# Schematic.net
KiCad netlist of a schematic drawn in Altium Designer
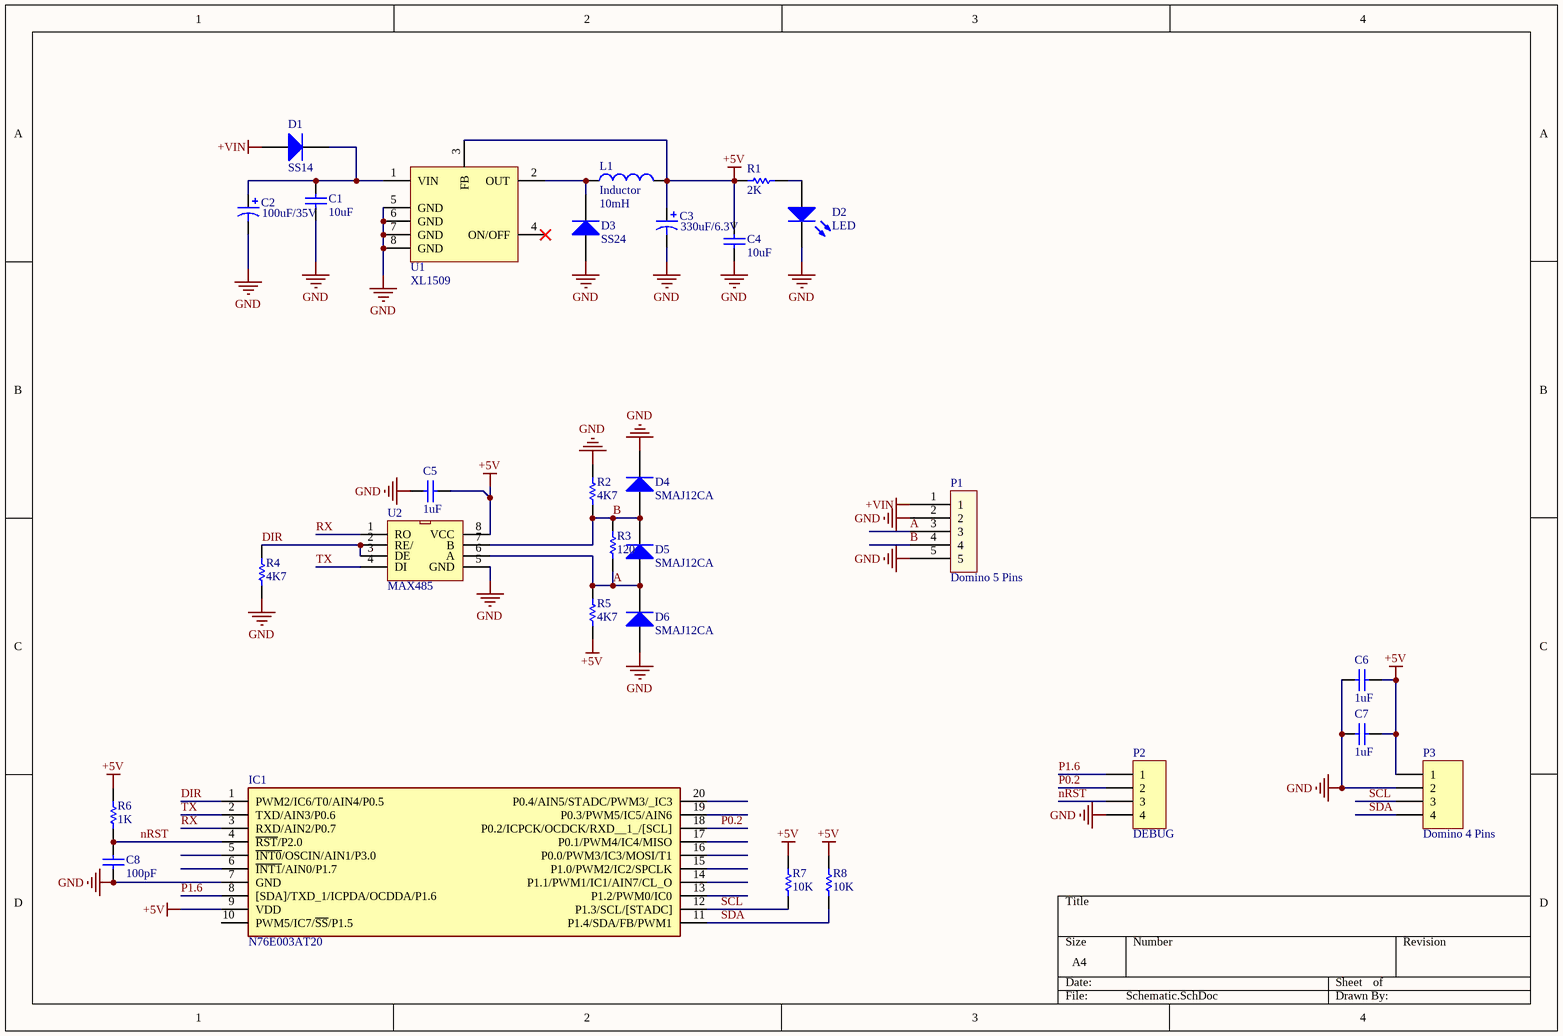
[diagram p0: Schematic.SchDoc]

(export (version "E")
  (design (tool "Eeschema 10.0.6"))
  (components
    (comp (ref "C1")
      (value "10uF")
      (footprint "MinhTien_PcbLib:CAPC1608L")
      (description "Capacitor")
      (fields (field (name "PUBLISHER") "Altium Limited"))
      (libsource (lib "MinhTien_SCHLib") (part "Cap"))
    )
    (comp (ref "C2")
      (value "100uF/35V")
      (footprint "MinhTien_PcbLib:Tu Nhom SMD_D8 6.3x7.7mm")
      (description "Polarized Capacitor (Axial)")
      (fields (field (name "Comment") "Cap Pol2") (field (name "PUBLISHER") "Altium Limited"))
      (libsource (lib "MinhTien_SCHLib") (part "Cap Pol2"))
    )
    (comp (ref "C3")
      (value "330uF/6.3V")
      (footprint "MinhTien_PcbLib:Tu Nhom SMD_D8 6.3x7.7mm")
      (description "Polarized Capacitor (Axial)")
      (fields (field (name "Comment") "Cap Pol2") (field (name "PUBLISHER") "Altium Limited"))
      (libsource (lib "MinhTien_SCHLib") (part "Cap Pol2"))
    )
    (comp (ref "C4")
      (value "10uF")
      (footprint "MinhTien_PcbLib:CAPC1608L")
      (description "Capacitor")
      (fields (field (name "PUBLISHER") "Altium Limited"))
      (libsource (lib "MinhTien_SCHLib") (part "Cap"))
    )
    (comp (ref "C5")
      (value "1uF")
      (footprint "MinhTien_PcbLib:CAPC1608L")
      (description "Capacitor")
      (fields (field (name "PUBLISHER") "Altium Limited"))
      (libsource (lib "MinhTien_SCHLib") (part "Cap"))
    )
    (comp (ref "C6")
      (value "1uF")
      (footprint "MinhTien_PcbLib:CAPC1608L")
      (description "Capacitor")
      (fields (field (name "PUBLISHER") "Altium Limited"))
      (libsource (lib "MinhTien_SCHLib") (part "Cap"))
    )
    (comp (ref "C7")
      (value "1uF")
      (footprint "MinhTien_PcbLib:CAPC1608L")
      (description "Capacitor")
      (fields (field (name "PUBLISHER") "Altium Limited"))
      (libsource (lib "MinhTien_SCHLib") (part "Cap"))
    )
    (comp (ref "C8")
      (value "100pF")
      (footprint "MinhTien_PcbLib:CAPC1608L")
      (description "Capacitor")
      (fields (field (name "PUBLISHER") "Altium Limited"))
      (libsource (lib "MinhTien_SCHLib") (part "Cap"))
    )
    (comp (ref "D1")
      (value "SS14")
      (footprint "MinhTien_PcbLib:DO-214AC")
      (description "Default Diode")
      (fields (field (name "PUBLISHER") "Altium Limited"))
      (libsource (lib "MinhTien_SCHLib") (part "Diode"))
    )
    (comp (ref "D2")
      (value "LED")
      (footprint "MinhTien_PcbLib:LED_SMD_0805_GREEN")
      (description "Typical INFRARED GaAs LED")
      (fields (field (name "PUBLISHER") "Altium Limited"))
      (libsource (lib "MinhTien_SCHLib") (part "LED"))
    )
    (comp (ref "D3")
      (value "SS24")
      (footprint "MinhTien_PcbLib:DO-214AC")
      (description "Default Diode")
      (fields (field (name "PUBLISHER") "Altium Limited"))
      (libsource (lib "MinhTien_SCHLib") (part "Diode"))
    )
    (comp (ref "D4")
      (value "SMAJ12CA")
      (footprint "MinhTien_PcbLib:DO-214AC")
      (description "Default Diode")
      (fields (field (name "PUBLISHER") "Altium Limited"))
      (libsource (lib "MinhTien_SCHLib") (part "Diode"))
    )
    (comp (ref "D5")
      (value "SMAJ12CA")
      (footprint "MinhTien_PcbLib:DO-214AC")
      (description "Default Diode")
      (fields (field (name "PUBLISHER") "Altium Limited"))
      (libsource (lib "MinhTien_SCHLib") (part "Diode"))
    )
    (comp (ref "D6")
      (value "SMAJ12CA")
      (footprint "MinhTien_PcbLib:DO-214AC")
      (description "Default Diode")
      (fields (field (name "PUBLISHER") "Altium Limited"))
      (libsource (lib "MinhTien_SCHLib") (part "Diode"))
    )
    (comp (ref "IC1")
      (value "N76E003AT20")
      (footprint "SamacSys:SOP65P640X120-20N")
      (description "Integrated Circuit")
      (libsource (lib "*") (part "N76E003AT20"))
    )
    (comp (ref "L1")
      (value "Inductor")
      (footprint "MinhTien_PCBLib:INDC585232L_CD53")
      (fields (field (name "ALTIUM_VALUE") "10mH") (field (name "PUBLISHER") "Altium Limited"))
      (libsource (lib "MinhTien_SCHLib") (part "Inductor"))
    )
    (comp (ref "P1")
      (value "Domino 5 Pins")
      (footprint "DOMINO_5PIN_5.08MM")
      (libsource (lib "MinhTien_SCHLib") (part "Domino 5 Pins"))
    )
    (comp (ref "P2")
      (value "DEBUG")
      (footprint "HDR1X4")
      (libsource (lib "MinhTien_SCHLib") (part "Connector_4pin"))
    )
    (comp (ref "P3")
      (value "Domino 4 Pins")
      (footprint "MinhTien_PCBLib:DOMINO_4PIN_5.08mm")
      (libsource (lib "MinhTien_SCHLib") (part "Domino 4 pin"))
    )
    (comp (ref "R1")
      (value "2K")
      (footprint "MinhTien_PcbLib:RESC1608L")
      (description "Semiconductor Resistor")
      (fields (field (name "PUBLISHER") "Altium Limited"))
      (libsource (lib "MinhTien_SCHLib") (part "Resistor"))
    )
    (comp (ref "R2")
      (value "4K7")
      (footprint "MinhTien_PcbLib:RESC1608L")
      (description "Semiconductor Resistor")
      (fields (field (name "PUBLISHER") "Altium Limited"))
      (libsource (lib "MinhTien_SCHLib") (part "Resistor"))
    )
    (comp (ref "R3")
      (value "120")
      (footprint "MinhTien_PcbLib:RESC1608L")
      (description "Semiconductor Resistor")
      (fields (field (name "PUBLISHER") "Altium Limited"))
      (libsource (lib "MinhTien_SCHLib") (part "Resistor"))
    )
    (comp (ref "R4")
      (value "4K7")
      (footprint "MinhTien_PcbLib:RESC1608L")
      (description "Semiconductor Resistor")
      (fields (field (name "PUBLISHER") "Altium Limited"))
      (libsource (lib "MinhTien_SCHLib") (part "Resistor"))
    )
    (comp (ref "R5")
      (value "4K7")
      (footprint "MinhTien_PcbLib:RESC1608L")
      (description "Semiconductor Resistor")
      (fields (field (name "PUBLISHER") "Altium Limited"))
      (libsource (lib "MinhTien_SCHLib") (part "Resistor"))
    )
    (comp (ref "R6")
      (value "1K")
      (footprint "RESC1608L")
      (description "Semiconductor Resistor")
      (fields (field (name "PUBLISHER") "Altium Limited"))
      (libsource (lib "MinhTien_SCHLib") (part "Resistor"))
    )
    (comp (ref "R7")
      (value "10K")
      (footprint "MinhTien_PcbLib:RESC1608L")
      (description "Semiconductor Resistor")
      (fields (field (name "PUBLISHER") "Altium Limited"))
      (libsource (lib "MinhTien_SCHLib") (part "Resistor"))
    )
    (comp (ref "R8")
      (value "10K")
      (footprint "MinhTien_PcbLib:RESC1608L")
      (description "Semiconductor Resistor")
      (fields (field (name "PUBLISHER") "Altium Limited"))
      (libsource (lib "MinhTien_SCHLib") (part "Resistor"))
    )
    (comp (ref "U1")
      (value "XL1509")
      (footprint "MinhTien_PcbLib:SOP8_L")
      (description "2A 150KHz 40V Buck DC to DC Converter")
      (libsource (lib "MinhTien_SCHLib") (part "XL1509"))
    )
    (comp (ref "U2")
      (value "MAX485")
      (footprint "MinhTien_PcbLib:SOP8_L")
      (libsource (lib "MinhTien_SCHLib") (part "MAX485"))
    )
  )
  (nets
    (net (code "1") (name "+5V") (class "Default")
      (node (ref "C3") (pin "1") (pinfunction "1_1") (pintype "passive"))
      (node (ref "C4") (pin "2") (pinfunction "2_2") (pintype "passive"))
      (node (ref "C5") (pin "1") (pinfunction "1_1") (pintype "passive"))
      (node (ref "C6") (pin "2") (pinfunction "2_2") (pintype "passive"))
      (node (ref "C7") (pin "2") (pinfunction "2_2") (pintype "passive"))
      (node (ref "IC1") (pin "9") (pinfunction "VDD_9") (pintype "passive"))
      (node (ref "L1") (pin "2") (pinfunction "2_2") (pintype "passive"))
      (node (ref "P3") (pin "1") (pinfunction "1_1") (pintype "passive"))
      (node (ref "R1") (pin "1") (pinfunction "1_1") (pintype "passive"))
      (node (ref "R5") (pin "1") (pinfunction "1_1") (pintype "passive"))
      (node (ref "R6") (pin "2") (pinfunction "2_2") (pintype "passive"))
      (node (ref "R7") (pin "2") (pinfunction "2_2") (pintype "passive"))
      (node (ref "R8") (pin "2") (pinfunction "2_2") (pintype "passive"))
      (node (ref "U1") (pin "3") (pinfunction "FB_3") (pintype "power_in"))
      (node (ref "U2") (pin "8") (pinfunction "VCC_8") (pintype "power_in"))
    )
    (net (code "2") (name "+VIN") (class "Default")
      (node (ref "D1") (pin "1") (pinfunction "A_1") (pintype "passive"))
      (node (ref "P1") (pin "1") (pinfunction "1_1") (pintype "passive"))
    )
    (net (code "3") (name "/A") (class "Default")
      (node (ref "D5") (pin "1") (pinfunction "A_1") (pintype "passive"))
      (node (ref "D6") (pin "2") (pinfunction "K_2") (pintype "passive"))
      (node (ref "P1") (pin "3") (pinfunction "3_3") (pintype "passive"))
      (node (ref "R3") (pin "1") (pinfunction "1_1") (pintype "passive"))
      (node (ref "R5") (pin "2") (pinfunction "2_2") (pintype "passive"))
      (node (ref "U2") (pin "6") (pinfunction "A_6") (pintype "power_in"))
    )
    (net (code "4") (name "/B") (class "Default")
      (node (ref "D4") (pin "1") (pinfunction "A_1") (pintype "passive"))
      (node (ref "D5") (pin "2") (pinfunction "K_2") (pintype "passive"))
      (node (ref "P1") (pin "4") (pinfunction "4_4") (pintype "passive"))
      (node (ref "R2") (pin "1") (pinfunction "1_1") (pintype "passive"))
      (node (ref "R3") (pin "2") (pinfunction "2_2") (pintype "passive"))
      (node (ref "U2") (pin "7") (pinfunction "B_7") (pintype "power_in"))
    )
    (net (code "5") (name "/DIR") (class "Default")
      (node (ref "IC1") (pin "1") (pinfunction "PWM2/IC6/T0/AIN4/P0.5_1") (pintype "passive"))
      (node (ref "R4") (pin "2") (pinfunction "2_2") (pintype "passive"))
      (node (ref "U2") (pin "2") (pinfunction "RE/_2") (pintype "power_in"))
      (node (ref "U2") (pin "3") (pinfunction "DE_3") (pintype "power_in"))
    )
    (net (code "6") (name "/P0.2") (class "Default")
      (node (ref "IC1") (pin "18") (pinfunction "P0.2/ICPCK/OCDCK/RXD__1_/[SCL]_18") (pintype "passive"))
      (node (ref "P2") (pin "2") (pinfunction "2_2") (pintype "passive"))
    )
    (net (code "7") (name "/P1.6") (class "Default")
      (node (ref "IC1") (pin "8") (pinfunction "[SDA]/TXD_1/ICPDA/OCDDA/P1.6_8") (pintype "passive"))
      (node (ref "P2") (pin "1") (pinfunction "1_1") (pintype "passive"))
    )
    (net (code "8") (name "/RX") (class "Default")
      (node (ref "IC1") (pin "3") (pinfunction "RXD/AIN2/P0.7_3") (pintype "passive"))
      (node (ref "U2") (pin "1") (pinfunction "RO_1") (pintype "power_in"))
    )
    (net (code "9") (name "/SCL") (class "Default")
      (node (ref "IC1") (pin "12") (pinfunction "P1.3/SCL/[STADC]_12") (pintype "passive"))
      (node (ref "P3") (pin "3") (pinfunction "3_3") (pintype "passive"))
      (node (ref "R7") (pin "1") (pinfunction "1_1") (pintype "passive"))
    )
    (net (code "10") (name "/SDA") (class "Default")
      (node (ref "IC1") (pin "11") (pinfunction "P1.4/SDA/FB/PWM1_11") (pintype "passive"))
      (node (ref "P3") (pin "4") (pinfunction "4_4") (pintype "passive"))
      (node (ref "R8") (pin "1") (pinfunction "1_1") (pintype "passive"))
    )
    (net (code "11") (name "/TX") (class "Default")
      (node (ref "IC1") (pin "2") (pinfunction "TXD/AIN3/P0.6_2") (pintype "passive"))
      (node (ref "U2") (pin "4") (pinfunction "DI_4") (pintype "power_in"))
    )
    (net (code "12") (name "/nRST") (class "Default")
      (node (ref "C8") (pin "2") (pinfunction "2_2") (pintype "passive"))
      (node (ref "IC1") (pin "4") (pinfunction "~{RST}/P2.0_4") (pintype "passive"))
      (node (ref "P2") (pin "3") (pinfunction "3_3") (pintype "passive"))
      (node (ref "R6") (pin "1") (pinfunction "1_1") (pintype "passive"))
    )
    (net (code "13") (name "GND") (class "Default")
      (node (ref "C1") (pin "1") (pinfunction "1_1") (pintype "passive"))
      (node (ref "C2") (pin "2") (pinfunction "2_2") (pintype "passive"))
      (node (ref "C3") (pin "2") (pinfunction "2_2") (pintype "passive"))
      (node (ref "C4") (pin "1") (pinfunction "1_1") (pintype "passive"))
      (node (ref "C5") (pin "2") (pinfunction "2_2") (pintype "passive"))
      (node (ref "C6") (pin "1") (pinfunction "1_1") (pintype "passive"))
      (node (ref "C7") (pin "1") (pinfunction "1_1") (pintype "passive"))
      (node (ref "C8") (pin "1") (pinfunction "1_1") (pintype "passive"))
      (node (ref "D2") (pin "2") (pinfunction "K_2") (pintype "passive"))
      (node (ref "D3") (pin "1") (pinfunction "A_1") (pintype "passive"))
      (node (ref "D4") (pin "2") (pinfunction "K_2") (pintype "passive"))
      (node (ref "D6") (pin "1") (pinfunction "A_1") (pintype "passive"))
      (node (ref "IC1") (pin "7") (pinfunction "GND_7") (pintype "passive"))
      (node (ref "P1") (pin "2") (pinfunction "2_2") (pintype "passive"))
      (node (ref "P1") (pin "5") (pinfunction "5_5") (pintype "passive"))
      (node (ref "P2") (pin "4") (pinfunction "4_4") (pintype "passive"))
      (node (ref "P3") (pin "2") (pinfunction "2_2") (pintype "passive"))
      (node (ref "R2") (pin "2") (pinfunction "2_2") (pintype "passive"))
      (node (ref "R4") (pin "1") (pinfunction "1_1") (pintype "passive"))
      (node (ref "U1") (pin "5") (pinfunction "GND_5") (pintype "power_in"))
      (node (ref "U1") (pin "6") (pinfunction "GND_6") (pintype "power_in"))
      (node (ref "U1") (pin "7") (pinfunction "GND_7") (pintype "power_in"))
      (node (ref "U1") (pin "8") (pinfunction "GND_8") (pintype "power_in"))
      (node (ref "U2") (pin "5") (pinfunction "GND_5") (pintype "power_in"))
    )
    (net (code "14") (name "Net-(D1-K)") (class "Default")
      (node (ref "C1") (pin "2") (pinfunction "2_2") (pintype "passive"))
      (node (ref "C2") (pin "1") (pinfunction "1_1") (pintype "passive"))
      (node (ref "D1") (pin "2") (pinfunction "K_2") (pintype "passive"))
      (node (ref "U1") (pin "1") (pinfunction "VIN_1") (pintype "power_in"))
    )
    (net (code "15") (name "Net-(D2-A)") (class "Default")
      (node (ref "D2") (pin "1") (pinfunction "A_1") (pintype "passive"))
      (node (ref "R1") (pin "2") (pinfunction "2_2") (pintype "passive"))
    )
    (net (code "16") (name "Net-(D3-K)") (class "Default")
      (node (ref "D3") (pin "2") (pinfunction "K_2") (pintype "passive"))
      (node (ref "L1") (pin "1") (pinfunction "1_1") (pintype "passive"))
      (node (ref "U1") (pin "2") (pinfunction "OUT_2") (pintype "power_in"))
    )
    (net (code "17") (name "unconnected-(IC1-P0.0{slash}PWM3{slash}IC3{slash}MOSI{slash}T1-Pad16)") (class "Default")
      (node (ref "IC1") (pin "16") (pinfunction "P0.0/PWM3/IC3/MOSI/T1_16") (pintype "passive"))
    )
    (net (code "18") (name "unconnected-(IC1-P0.1{slash}PWM4{slash}IC4{slash}MISO-Pad17)") (class "Default")
      (node (ref "IC1") (pin "17") (pinfunction "P0.1/PWM4/IC4/MISO_17") (pintype "passive"))
    )
    (net (code "19") (name "unconnected-(IC1-P0.3{slash}PWM5{slash}IC5{slash}AIN6-Pad19)") (class "Default")
      (node (ref "IC1") (pin "19") (pinfunction "P0.3/PWM5/IC5/AIN6_19") (pintype "passive"))
    )
    (net (code "20") (name "unconnected-(IC1-P0.4{slash}AIN5{slash}STADC{slash}PWM3{slash}_IC3-Pad20)") (class "Default")
      (node (ref "IC1") (pin "20") (pinfunction "P0.4/AIN5/STADC/PWM3/_IC3_20") (pintype "passive"))
    )
    (net (code "21") (name "unconnected-(IC1-P1.0{slash}PWM2{slash}IC2{slash}SPCLK-Pad15)") (class "Default")
      (node (ref "IC1") (pin "15") (pinfunction "P1.0/PWM2/IC2/SPCLK_15") (pintype "passive"))
    )
    (net (code "22") (name "unconnected-(IC1-P1.1{slash}PWM1{slash}IC1{slash}AIN7{slash}CL_O-Pad14)") (class "Default")
      (node (ref "IC1") (pin "14") (pinfunction "P1.1/PWM1/IC1/AIN7/CL_O_14") (pintype "passive"))
    )
    (net (code "23") (name "unconnected-(IC1-P1.2{slash}PWM0{slash}IC0-Pad13)") (class "Default")
      (node (ref "IC1") (pin "13") (pinfunction "P1.2/PWM0/IC0_13") (pintype "passive"))
    )
    (net (code "24") (name "unconnected-(IC1-PWM5{slash}IC7{slash}~{SS}{slash}P1.5-Pad10)") (class "Default")
      (node (ref "IC1") (pin "10") (pinfunction "PWM5/IC7/~{SS}/P1.5_10") (pintype "passive"))
    )
    (net (code "25") (name "unconnected-(IC1-~{INT0}{slash}OSCIN{slash}AIN1{slash}P3.0-Pad5)") (class "Default")
      (node (ref "IC1") (pin "5") (pinfunction "~{INT0}/OSCIN/AIN1/P3.0_5") (pintype "passive"))
    )
    (net (code "26") (name "unconnected-(IC1-~{INT1}{slash}AIN0{slash}P1.7-Pad6)") (class "Default")
      (node (ref "IC1") (pin "6") (pinfunction "~{INT1}/AIN0/P1.7_6") (pintype "passive"))
    )
    (net (code "27") (name "unconnected-(U1-ON{slash}OFF-Pad4)") (class "Default")
      (node (ref "U1") (pin "4") (pinfunction "ON/OFF_4") (pintype "power_in+no_connect"))
    )
  )
)
